# MOD-Y_V10.net
KiCad netlist of a schematic drawn in EAGLE
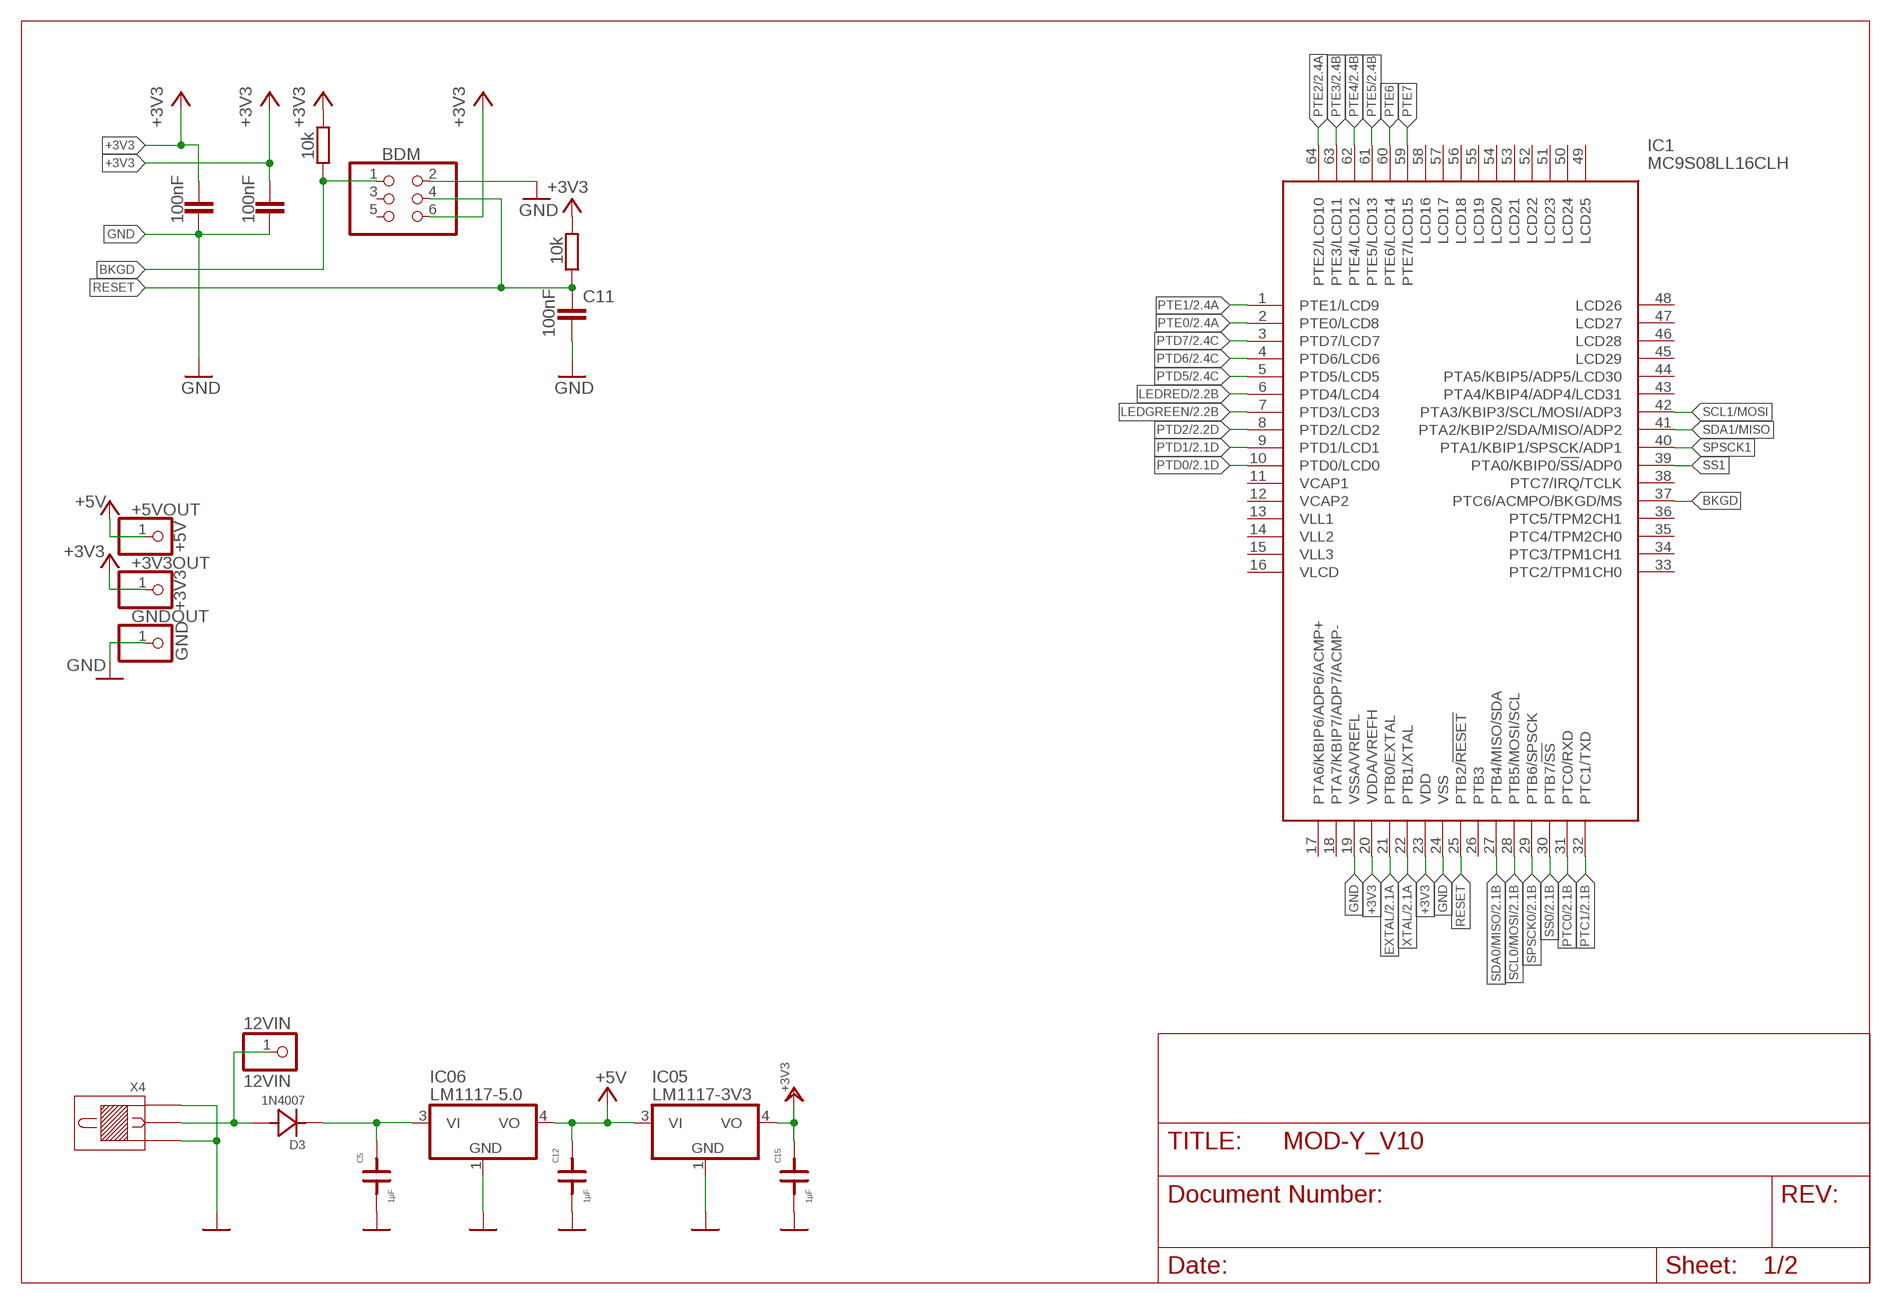
[diagram p0: schematic, sheet 1]
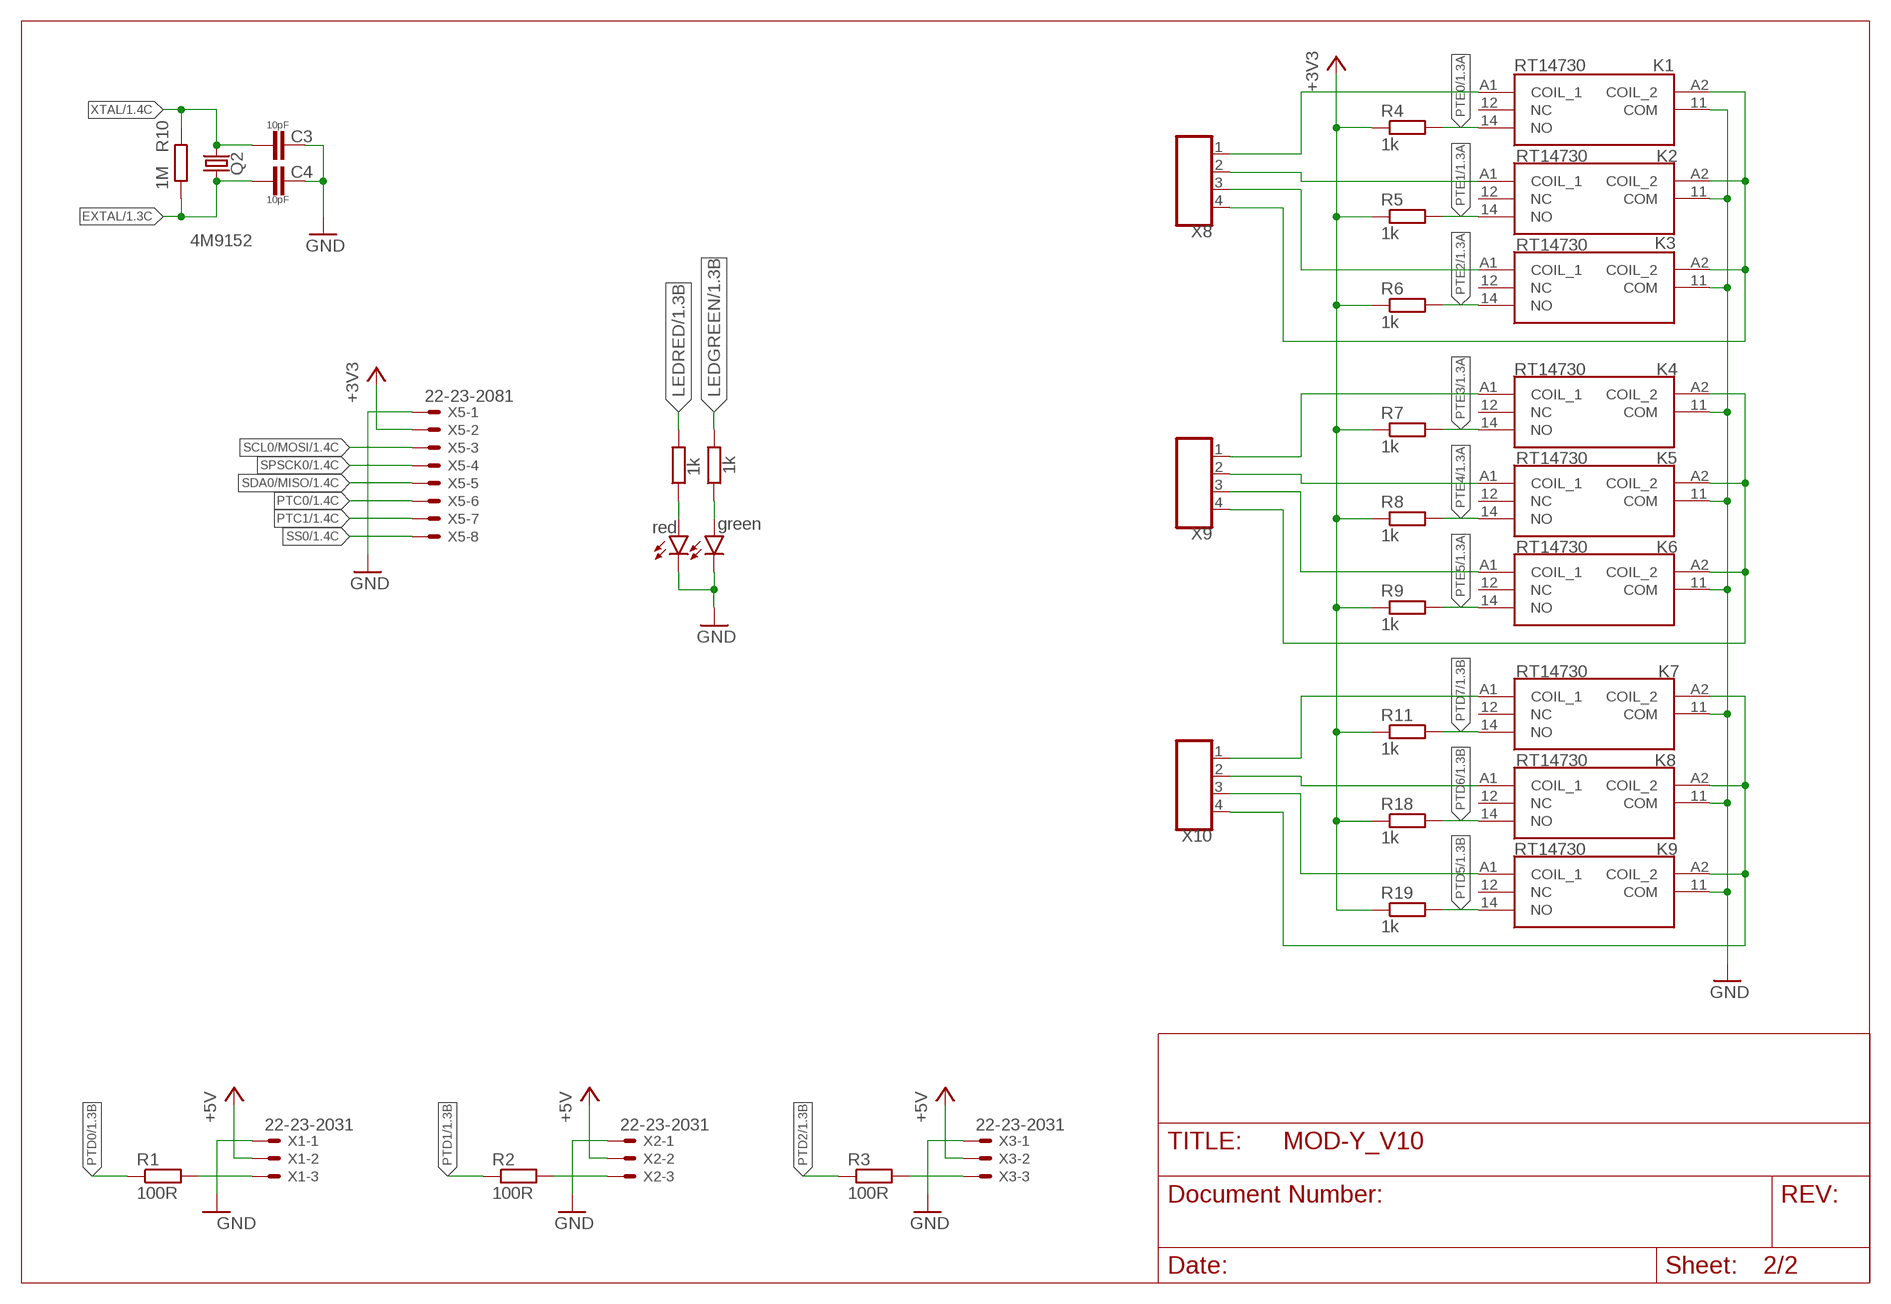
[diagram p1: schematic, sheet 2]

(export (version "E")
  (design (tool "Eeschema 10.0.6"))
  (components
    (comp (ref "+3V3OUT")
      (value "+3V3")
      (footprint "eagle-import:1X01")
      (libsource (lib "eagle-import") (part "PINHD-1X1"))
    )
    (comp (ref "+5VOUT")
      (value "+5V")
      (footprint "eagle-import:1X01")
      (libsource (lib "eagle-import") (part "PINHD-1X1"))
    )
    (comp (ref "12VIN")
      (value "12VIN")
      (footprint "eagle-import:1X01")
      (libsource (lib "eagle-import") (part "PINHD-1X1"))
    )
    (comp (ref "BDM")
      (value "PINHD-2X3")
      (footprint "eagle-import:2X03")
      (libsource (lib "eagle-import") (part "PINHD-2X3"))
    )
    (comp (ref "C5")
      (value "1µF")
      (footprint "eagle-import:0805F")
      (libsource (lib "eagle-import") (part "C1"))
    )
    (comp (ref "C9")
      (value "100nF")
      (footprint "eagle-import:C0805")
      (libsource (lib "eagle-import") (part "C-EUC0805"))
    )
    (comp (ref "C10")
      (value "100nF")
      (footprint "eagle-import:C0805")
      (libsource (lib "eagle-import") (part "C-EUC0805"))
    )
    (comp (ref "C11")
      (value "100nF")
      (footprint "eagle-import:C0805")
      (libsource (lib "eagle-import") (part "C-EUC0805"))
    )
    (comp (ref "C12")
      (value "1µF")
      (footprint "eagle-import:0805F")
      (libsource (lib "eagle-import") (part "C1"))
    )
    (comp (ref "C15")
      (value "1µF")
      (footprint "eagle-import:0805F")
      (libsource (lib "eagle-import") (part "C1"))
    )
    (comp (ref "D3")
      (value "1N4007")
      (footprint "eagle-import:MELF_B")
      (libsource (lib "eagle-import") (part "DHCMELF"))
    )
    (comp (ref "GNDOUT")
      (value "GND")
      (footprint "eagle-import:1X01")
      (libsource (lib "eagle-import") (part "PINHD-1X1"))
    )
    (comp (ref "IC1")
      (value "MC9S08LL16CLH")
      (footprint "eagle-import:QFP50P1200X1200X160-64N")
      (fields (field (name "MOUSER_PART_NUMBER") "841-MC9S08LL16CLH"))
      (libsource (lib "eagle-import") (part "MC9S08LL16CLH"))
    )
    (comp (ref "IC05")
      (value "LM1117-3V3")
      (footprint "eagle-import:DPAK")
      (libsource (lib "eagle-import") (part "LM1117DT"))
    )
    (comp (ref "IC06")
      (value "LM1117-5.0")
      (footprint "eagle-import:DPAK")
      (libsource (lib "eagle-import") (part "LM1117DT"))
    )
    (comp (ref "R16")
      (value "10k")
      (footprint "eagle-import:R0805")
      (libsource (lib "eagle-import") (part "R-EU_R0805"))
    )
    (comp (ref "R17")
      (value "10k")
      (footprint "eagle-import:R0805")
      (libsource (lib "eagle-import") (part "R-EU_R0805"))
    )
    (comp (ref "X4")
      (value "SPP")
      (footprint "eagle-import:SPP")
      (libsource (lib "eagle-import") (part "SPP"))
    )
    (comp (ref "C3")
      (value "10pF")
      (footprint "eagle-import:C0805")
      (libsource (lib "eagle-import") (part "C-EUC0805"))
    )
    (comp (ref "C4")
      (value "10pF")
      (footprint "eagle-import:C0805")
      (libsource (lib "eagle-import") (part "C-EUC0805"))
    )
    (comp (ref "K1")
      (value "RT14730")
      (footprint "eagle-import:RT14730")
      (fields (field (name "MANUFACTURER_PART_NUMBER") "rt14730"))
      (libsource (lib "eagle-import") (part "RT14730"))
    )
    (comp (ref "K2")
      (value "RT14730")
      (footprint "eagle-import:RT14730")
      (fields (field (name "MANUFACTURER_PART_NUMBER") "rt14730"))
      (libsource (lib "eagle-import") (part "RT14730"))
    )
    (comp (ref "K3")
      (value "RT14730")
      (footprint "eagle-import:RT14730")
      (fields (field (name "MANUFACTURER_PART_NUMBER") "rt14730"))
      (libsource (lib "eagle-import") (part "RT14730"))
    )
    (comp (ref "K4")
      (value "RT14730")
      (footprint "eagle-import:RT14730")
      (fields (field (name "MANUFACTURER_PART_NUMBER") "rt14730"))
      (libsource (lib "eagle-import") (part "RT14730"))
    )
    (comp (ref "K5")
      (value "RT14730")
      (footprint "eagle-import:RT14730")
      (fields (field (name "MANUFACTURER_PART_NUMBER") "rt14730"))
      (libsource (lib "eagle-import") (part "RT14730"))
    )
    (comp (ref "K6")
      (value "RT14730")
      (footprint "eagle-import:RT14730")
      (fields (field (name "MANUFACTURER_PART_NUMBER") "rt14730"))
      (libsource (lib "eagle-import") (part "RT14730"))
    )
    (comp (ref "K7")
      (value "RT14730")
      (footprint "eagle-import:RT14730")
      (fields (field (name "MANUFACTURER_PART_NUMBER") "rt14730"))
      (libsource (lib "eagle-import") (part "RT14730"))
    )
    (comp (ref "K8")
      (value "RT14730")
      (footprint "eagle-import:RT14730")
      (fields (field (name "MANUFACTURER_PART_NUMBER") "rt14730"))
      (libsource (lib "eagle-import") (part "RT14730"))
    )
    (comp (ref "K9")
      (value "RT14730")
      (footprint "eagle-import:RT14730")
      (fields (field (name "MANUFACTURER_PART_NUMBER") "rt14730"))
      (libsource (lib "eagle-import") (part "RT14730"))
    )
    (comp (ref "LED1")
      (value "green")
      (footprint "eagle-import:CHIP-LED0805")
      (libsource (lib "eagle-import") (part "LEDCHIP-LED0805"))
    )
    (comp (ref "LED2")
      (value "red")
      (footprint "eagle-import:CHIP-LED0805")
      (libsource (lib "eagle-import") (part "LEDCHIP-LED0805"))
    )
    (comp (ref "Q2")
      (value "4M9152")
      (footprint "eagle-import:HC49UP")
      (libsource (lib "eagle-import") (part "CRYSTALHC49UP"))
    )
    (comp (ref "R1")
      (value "100R")
      (footprint "eagle-import:R0805")
      (libsource (lib "eagle-import") (part "R-EU_R0805"))
    )
    (comp (ref "R2")
      (value "100R")
      (footprint "eagle-import:R0805")
      (libsource (lib "eagle-import") (part "R-EU_R0805"))
    )
    (comp (ref "R3")
      (value "100R")
      (footprint "eagle-import:R0805")
      (libsource (lib "eagle-import") (part "R-EU_R0805"))
    )
    (comp (ref "R4")
      (value "1k")
      (footprint "eagle-import:R0805")
      (libsource (lib "eagle-import") (part "R-EU_R0805"))
    )
    (comp (ref "R5")
      (value "1k")
      (footprint "eagle-import:R0805")
      (libsource (lib "eagle-import") (part "R-EU_R0805"))
    )
    (comp (ref "R6")
      (value "1k")
      (footprint "eagle-import:R0805")
      (libsource (lib "eagle-import") (part "R-EU_R0805"))
    )
    (comp (ref "R7")
      (value "1k")
      (footprint "eagle-import:R0805")
      (libsource (lib "eagle-import") (part "R-EU_R0805"))
    )
    (comp (ref "R8")
      (value "1k")
      (footprint "eagle-import:R0805")
      (libsource (lib "eagle-import") (part "R-EU_R0805"))
    )
    (comp (ref "R9")
      (value "1k")
      (footprint "eagle-import:R0805")
      (libsource (lib "eagle-import") (part "R-EU_R0805"))
    )
    (comp (ref "R10")
      (value "1M")
      (footprint "eagle-import:R0805")
      (libsource (lib "eagle-import") (part "R-EU_R0805"))
    )
    (comp (ref "R11")
      (value "1k")
      (footprint "eagle-import:R0805")
      (libsource (lib "eagle-import") (part "R-EU_R0805"))
    )
    (comp (ref "R12")
      (value "1k")
      (footprint "eagle-import:R0805")
      (libsource (lib "eagle-import") (part "R-EU_R0805"))
    )
    (comp (ref "R13")
      (value "1k")
      (footprint "eagle-import:R0805")
      (libsource (lib "eagle-import") (part "R-EU_R0805"))
    )
    (comp (ref "R18")
      (value "1k")
      (footprint "eagle-import:R0805")
      (libsource (lib "eagle-import") (part "R-EU_R0805"))
    )
    (comp (ref "R19")
      (value "1k")
      (footprint "eagle-import:R0805")
      (libsource (lib "eagle-import") (part "R-EU_R0805"))
    )
    (comp (ref "X1")
      (value "22-23-2031")
      (footprint "eagle-import:22-23-2031")
      (fields (field (name "MF") "MOLEX"))
      (libsource (lib "eagle-import") (part "22-23-2031"))
    )
    (comp (ref "X2")
      (value "22-23-2031")
      (footprint "eagle-import:22-23-2031")
      (fields (field (name "MF") "MOLEX"))
      (libsource (lib "eagle-import") (part "22-23-2031"))
    )
    (comp (ref "X3")
      (value "22-23-2031")
      (footprint "eagle-import:22-23-2031")
      (fields (field (name "MF") "MOLEX"))
      (libsource (lib "eagle-import") (part "22-23-2031"))
    )
    (comp (ref "X5")
      (value "22-23-2081")
      (footprint "eagle-import:22-23-2081")
      (fields (field (name "MF") "MOLEX"))
      (libsource (lib "eagle-import") (part "22-23-2081"))
    )
    (comp (ref "X8")
      (value "KLEMME4")
      (footprint "eagle-import:KLEMME4")
      (libsource (lib "eagle-import") (part "KLEMME4"))
    )
    (comp (ref "X9")
      (value "KLEMME4")
      (footprint "eagle-import:KLEMME4")
      (libsource (lib "eagle-import") (part "KLEMME4"))
    )
    (comp (ref "X10")
      (value "KLEMME4")
      (footprint "eagle-import:KLEMME4")
      (libsource (lib "eagle-import") (part "KLEMME4"))
    )
  )
  (nets
    (net (code "1") (name "+3V3") (class "Default")
      (node (ref "+3V3OUT") (pin "1") (pinfunction "1_1") (pintype "passive"))
      (node (ref "BDM") (pin "6") (pinfunction "6_6") (pintype "passive"))
      (node (ref "C10") (pin "1") (pinfunction "1_1") (pintype "passive"))
      (node (ref "C15") (pin "2") (pinfunction "2_2") (pintype "bidirectional"))
      (node (ref "C9") (pin "1") (pinfunction "1_1") (pintype "passive"))
      (node (ref "IC05") (pin "4") (pinfunction "VO_4") (pintype "output"))
      (node (ref "IC1") (pin "20") (pinfunction "VDDA/VREFH_20") (pintype "bidirectional"))
      (node (ref "IC1") (pin "23") (pinfunction "VDD_23") (pintype "bidirectional"))
      (node (ref "R11") (pin "1") (pinfunction "1_1") (pintype "passive"))
      (node (ref "R16") (pin "2") (pinfunction "2_2") (pintype "passive"))
      (node (ref "R17") (pin "2") (pinfunction "2_2") (pintype "passive"))
      (node (ref "R18") (pin "1") (pinfunction "1_1") (pintype "passive"))
      (node (ref "R19") (pin "1") (pinfunction "1_1") (pintype "passive"))
      (node (ref "R4") (pin "1") (pinfunction "1_1") (pintype "passive"))
      (node (ref "R5") (pin "1") (pinfunction "1_1") (pintype "passive"))
      (node (ref "R6") (pin "1") (pinfunction "1_1") (pintype "passive"))
      (node (ref "R7") (pin "1") (pinfunction "1_1") (pintype "passive"))
      (node (ref "R8") (pin "1") (pinfunction "1_1") (pintype "passive"))
      (node (ref "R9") (pin "1") (pinfunction "1_1") (pintype "passive"))
      (node (ref "X5") (pin "2") (pinfunction "S_2") (pintype "passive"))
    )
    (net (code "2") (name "+5V") (class "Default")
      (node (ref "+5VOUT") (pin "1") (pinfunction "1_1") (pintype "passive"))
      (node (ref "C12") (pin "2") (pinfunction "2_2") (pintype "bidirectional"))
      (node (ref "IC05") (pin "3") (pinfunction "VI_3") (pintype "input"))
      (node (ref "IC06") (pin "4") (pinfunction "VO_4") (pintype "output"))
      (node (ref "X1") (pin "2") (pinfunction "S_2") (pintype "passive"))
      (node (ref "X2") (pin "2") (pinfunction "S_2") (pintype "passive"))
      (node (ref "X3") (pin "2") (pinfunction "S_2") (pintype "passive"))
    )
    (net (code "3") (name "BKGD") (class "Default")
      (node (ref "BDM") (pin "1") (pinfunction "1_1") (pintype "passive"))
      (node (ref "IC1") (pin "37") (pinfunction "PTC6/ACMPO/BKGD/MS_37") (pintype "bidirectional"))
      (node (ref "R16") (pin "1") (pinfunction "1_1") (pintype "passive"))
    )
    (net (code "4") (name "EXTAL") (class "Default")
      (node (ref "C4") (pin "1") (pinfunction "1_1") (pintype "passive"))
      (node (ref "IC1") (pin "21") (pinfunction "PTB0/EXTAL_21") (pintype "bidirectional"))
      (node (ref "Q2") (pin "1") (pinfunction "1_1") (pintype "passive"))
      (node (ref "R10") (pin "1") (pinfunction "1_1") (pintype "passive"))
    )
    (net (code "5") (name "GND") (class "Default")
      (node (ref "BDM") (pin "2") (pinfunction "2_2") (pintype "passive"))
      (node (ref "C10") (pin "2") (pinfunction "2_2") (pintype "passive"))
      (node (ref "C11") (pin "2") (pinfunction "2_2") (pintype "passive"))
      (node (ref "C12") (pin "1") (pinfunction "1_1") (pintype "bidirectional"))
      (node (ref "C15") (pin "1") (pinfunction "1_1") (pintype "bidirectional"))
      (node (ref "C3") (pin "2") (pinfunction "2_2") (pintype "passive"))
      (node (ref "C4") (pin "2") (pinfunction "2_2") (pintype "passive"))
      (node (ref "C5") (pin "1") (pinfunction "1_1") (pintype "bidirectional"))
      (node (ref "C9") (pin "2") (pinfunction "2_2") (pintype "passive"))
      (node (ref "GNDOUT") (pin "1") (pinfunction "1_1") (pintype "passive"))
      (node (ref "IC05") (pin "1") (pinfunction "GND_1") (pintype "input"))
      (node (ref "IC06") (pin "1") (pinfunction "GND_1") (pintype "input"))
      (node (ref "IC1") (pin "19") (pinfunction "VSSA/VREFL_19") (pintype "bidirectional"))
      (node (ref "IC1") (pin "24") (pinfunction "VSS_24") (pintype "bidirectional"))
      (node (ref "K1") (pin "11") (pinfunction "COM_11") (pintype "bidirectional"))
      (node (ref "K2") (pin "11") (pinfunction "COM_11") (pintype "bidirectional"))
      (node (ref "K3") (pin "11") (pinfunction "COM_11") (pintype "bidirectional"))
      (node (ref "K4") (pin "11") (pinfunction "COM_11") (pintype "bidirectional"))
      (node (ref "K5") (pin "11") (pinfunction "COM_11") (pintype "bidirectional"))
      (node (ref "K6") (pin "11") (pinfunction "COM_11") (pintype "bidirectional"))
      (node (ref "K7") (pin "11") (pinfunction "COM_11") (pintype "bidirectional"))
      (node (ref "K8") (pin "11") (pinfunction "COM_11") (pintype "bidirectional"))
      (node (ref "K9") (pin "11") (pinfunction "COM_11") (pintype "bidirectional"))
      (node (ref "LED1") (pin "C") (pinfunction "C_C") (pintype "passive"))
      (node (ref "LED2") (pin "C") (pinfunction "C_C") (pintype "passive"))
      (node (ref "X1") (pin "1") (pinfunction "S_1") (pintype "passive"))
      (node (ref "X2") (pin "1") (pinfunction "S_1") (pintype "passive"))
      (node (ref "X3") (pin "1") (pinfunction "S_1") (pintype "passive"))
      (node (ref "X4") (pin "1") (pinfunction "1_1") (pintype "bidirectional"))
      (node (ref "X4") (pin "3") (pinfunction "3_3") (pintype "bidirectional"))
      (node (ref "X5") (pin "1") (pinfunction "S_1") (pintype "passive"))
    )
    (net (code "6") (name "LEDGREEN") (class "Default")
      (node (ref "IC1") (pin "7") (pinfunction "PTD3/LCD3_7") (pintype "bidirectional"))
      (node (ref "R13") (pin "2") (pinfunction "2_2") (pintype "passive"))
    )
    (net (code "7") (name "LEDRED") (class "Default")
      (node (ref "IC1") (pin "6") (pinfunction "PTD4/LCD4_6") (pintype "bidirectional"))
      (node (ref "R12") (pin "2") (pinfunction "2_2") (pintype "passive"))
    )
    (net (code "8") (name "Net-(12VIN-Pad1)") (class "Default")
      (node (ref "12VIN") (pin "1") (pinfunction "1_1") (pintype "passive"))
      (node (ref "D3") (pin "A") (pinfunction "A_A") (pintype "bidirectional"))
      (node (ref "X4") (pin "2") (pinfunction "2_2") (pintype "bidirectional"))
    )
    (net (code "9") (name "Net-(IC06-VI)") (class "Default")
      (node (ref "C5") (pin "2") (pinfunction "2_2") (pintype "bidirectional"))
      (node (ref "D3") (pin "K") (pinfunction "K_K") (pintype "bidirectional"))
      (node (ref "IC06") (pin "3") (pinfunction "VI_3") (pintype "input"))
    )
    (net (code "10") (name "Net-(K1-COIL_1)") (class "Default")
      (node (ref "K1") (pin "A1") (pinfunction "COIL_1_A1") (pintype "bidirectional"))
      (node (ref "X8") (pin "1") (pinfunction "1_1") (pintype "bidirectional"))
    )
    (net (code "11") (name "Net-(K1-COIL_2)") (class "Default")
      (node (ref "K1") (pin "A2") (pinfunction "COIL_2_A2") (pintype "bidirectional"))
      (node (ref "K2") (pin "A2") (pinfunction "COIL_2_A2") (pintype "bidirectional"))
      (node (ref "K3") (pin "A2") (pinfunction "COIL_2_A2") (pintype "bidirectional"))
      (node (ref "X8") (pin "4") (pinfunction "4_4") (pintype "bidirectional"))
    )
    (net (code "12") (name "Net-(K2-COIL_1)") (class "Default")
      (node (ref "K2") (pin "A1") (pinfunction "COIL_1_A1") (pintype "bidirectional"))
      (node (ref "X8") (pin "2") (pinfunction "2_2") (pintype "bidirectional"))
    )
    (net (code "13") (name "Net-(K3-COIL_1)") (class "Default")
      (node (ref "K3") (pin "A1") (pinfunction "COIL_1_A1") (pintype "bidirectional"))
      (node (ref "X8") (pin "3") (pinfunction "3_3") (pintype "bidirectional"))
    )
    (net (code "14") (name "Net-(K4-COIL_1)") (class "Default")
      (node (ref "K4") (pin "A1") (pinfunction "COIL_1_A1") (pintype "bidirectional"))
      (node (ref "X9") (pin "1") (pinfunction "1_1") (pintype "bidirectional"))
    )
    (net (code "15") (name "Net-(K4-COIL_2)") (class "Default")
      (node (ref "K4") (pin "A2") (pinfunction "COIL_2_A2") (pintype "bidirectional"))
      (node (ref "K5") (pin "A2") (pinfunction "COIL_2_A2") (pintype "bidirectional"))
      (node (ref "K6") (pin "A2") (pinfunction "COIL_2_A2") (pintype "bidirectional"))
      (node (ref "X9") (pin "4") (pinfunction "4_4") (pintype "bidirectional"))
    )
    (net (code "16") (name "Net-(K5-COIL_1)") (class "Default")
      (node (ref "K5") (pin "A1") (pinfunction "COIL_1_A1") (pintype "bidirectional"))
      (node (ref "X9") (pin "2") (pinfunction "2_2") (pintype "bidirectional"))
    )
    (net (code "17") (name "Net-(K6-COIL_1)") (class "Default")
      (node (ref "K6") (pin "A1") (pinfunction "COIL_1_A1") (pintype "bidirectional"))
      (node (ref "X9") (pin "3") (pinfunction "3_3") (pintype "bidirectional"))
    )
    (net (code "18") (name "Net-(K7-COIL_1)") (class "Default")
      (node (ref "K7") (pin "A1") (pinfunction "COIL_1_A1") (pintype "bidirectional"))
      (node (ref "X10") (pin "1") (pinfunction "1_1") (pintype "bidirectional"))
    )
    (net (code "19") (name "Net-(K7-COIL_2)") (class "Default")
      (node (ref "K7") (pin "A2") (pinfunction "COIL_2_A2") (pintype "bidirectional"))
      (node (ref "K8") (pin "A2") (pinfunction "COIL_2_A2") (pintype "bidirectional"))
      (node (ref "K9") (pin "A2") (pinfunction "COIL_2_A2") (pintype "bidirectional"))
      (node (ref "X10") (pin "4") (pinfunction "4_4") (pintype "bidirectional"))
    )
    (net (code "20") (name "Net-(K8-COIL_1)") (class "Default")
      (node (ref "K8") (pin "A1") (pinfunction "COIL_1_A1") (pintype "bidirectional"))
      (node (ref "X10") (pin "2") (pinfunction "2_2") (pintype "bidirectional"))
    )
    (net (code "21") (name "Net-(K9-COIL_1)") (class "Default")
      (node (ref "K9") (pin "A1") (pinfunction "COIL_1_A1") (pintype "bidirectional"))
      (node (ref "X10") (pin "3") (pinfunction "3_3") (pintype "bidirectional"))
    )
    (net (code "22") (name "Net-(LED1-PadA)") (class "Default")
      (node (ref "LED1") (pin "A") (pinfunction "A_A") (pintype "passive"))
      (node (ref "R13") (pin "1") (pinfunction "1_1") (pintype "passive"))
    )
    (net (code "23") (name "Net-(LED2-PadA)") (class "Default")
      (node (ref "LED2") (pin "A") (pinfunction "A_A") (pintype "passive"))
      (node (ref "R12") (pin "1") (pinfunction "1_1") (pintype "passive"))
    )
    (net (code "24") (name "Net-(X1C-S)") (class "Default")
      (node (ref "R1") (pin "2") (pinfunction "2_2") (pintype "passive"))
      (node (ref "X1") (pin "3") (pinfunction "S_3") (pintype "passive"))
    )
    (net (code "25") (name "Net-(X2C-S)") (class "Default")
      (node (ref "R2") (pin "2") (pinfunction "2_2") (pintype "passive"))
      (node (ref "X2") (pin "3") (pinfunction "S_3") (pintype "passive"))
    )
    (net (code "26") (name "Net-(X3C-S)") (class "Default")
      (node (ref "R3") (pin "2") (pinfunction "2_2") (pintype "passive"))
      (node (ref "X3") (pin "3") (pinfunction "S_3") (pintype "passive"))
    )
    (net (code "27") (name "PTC0") (class "Default")
      (node (ref "IC1") (pin "31") (pinfunction "PTC0/RXD_31") (pintype "bidirectional"))
      (node (ref "X5") (pin "6") (pinfunction "S_6") (pintype "passive"))
    )
    (net (code "28") (name "PTC1") (class "Default")
      (node (ref "IC1") (pin "32") (pinfunction "PTC1/TXD_32") (pintype "bidirectional"))
      (node (ref "X5") (pin "7") (pinfunction "S_7") (pintype "passive"))
    )
    (net (code "29") (name "PTD0") (class "Default")
      (node (ref "IC1") (pin "10") (pinfunction "PTD0/LCD0_10") (pintype "bidirectional"))
      (node (ref "R1") (pin "1") (pinfunction "1_1") (pintype "passive"))
    )
    (net (code "30") (name "PTD1") (class "Default")
      (node (ref "IC1") (pin "9") (pinfunction "PTD1/LCD1_9") (pintype "bidirectional"))
      (node (ref "R2") (pin "1") (pinfunction "1_1") (pintype "passive"))
    )
    (net (code "31") (name "PTD2") (class "Default")
      (node (ref "IC1") (pin "8") (pinfunction "PTD2/LCD2_8") (pintype "bidirectional"))
      (node (ref "R3") (pin "1") (pinfunction "1_1") (pintype "passive"))
    )
    (net (code "32") (name "PTD5") (class "Default")
      (node (ref "IC1") (pin "5") (pinfunction "PTD5/LCD5_5") (pintype "bidirectional"))
      (node (ref "K9") (pin "14") (pinfunction "NO_14") (pintype "bidirectional"))
      (node (ref "R19") (pin "2") (pinfunction "2_2") (pintype "passive"))
    )
    (net (code "33") (name "PTD6") (class "Default")
      (node (ref "IC1") (pin "4") (pinfunction "PTD6/LCD6_4") (pintype "bidirectional"))
      (node (ref "K8") (pin "14") (pinfunction "NO_14") (pintype "bidirectional"))
      (node (ref "R18") (pin "2") (pinfunction "2_2") (pintype "passive"))
    )
    (net (code "34") (name "PTD7") (class "Default")
      (node (ref "IC1") (pin "3") (pinfunction "PTD7/LCD7_3") (pintype "bidirectional"))
      (node (ref "K7") (pin "14") (pinfunction "NO_14") (pintype "bidirectional"))
      (node (ref "R11") (pin "2") (pinfunction "2_2") (pintype "passive"))
    )
    (net (code "35") (name "PTE0") (class "Default")
      (node (ref "IC1") (pin "2") (pinfunction "PTE0/LCD8_2") (pintype "bidirectional"))
      (node (ref "K1") (pin "14") (pinfunction "NO_14") (pintype "bidirectional"))
      (node (ref "R4") (pin "2") (pinfunction "2_2") (pintype "passive"))
    )
    (net (code "36") (name "PTE1") (class "Default")
      (node (ref "IC1") (pin "1") (pinfunction "PTE1/LCD9_1") (pintype "bidirectional"))
      (node (ref "K2") (pin "14") (pinfunction "NO_14") (pintype "bidirectional"))
      (node (ref "R5") (pin "2") (pinfunction "2_2") (pintype "passive"))
    )
    (net (code "37") (name "PTE2") (class "Default")
      (node (ref "IC1") (pin "64") (pinfunction "PTE2/LCD10_64") (pintype "bidirectional"))
      (node (ref "K3") (pin "14") (pinfunction "NO_14") (pintype "bidirectional"))
      (node (ref "R6") (pin "2") (pinfunction "2_2") (pintype "passive"))
    )
    (net (code "38") (name "PTE3") (class "Default")
      (node (ref "IC1") (pin "63") (pinfunction "PTE3/LCD11_63") (pintype "bidirectional"))
      (node (ref "K4") (pin "14") (pinfunction "NO_14") (pintype "bidirectional"))
      (node (ref "R7") (pin "2") (pinfunction "2_2") (pintype "passive"))
    )
    (net (code "39") (name "PTE4") (class "Default")
      (node (ref "IC1") (pin "62") (pinfunction "PTE4/LCD12_62") (pintype "bidirectional"))
      (node (ref "K5") (pin "14") (pinfunction "NO_14") (pintype "bidirectional"))
      (node (ref "R8") (pin "2") (pinfunction "2_2") (pintype "passive"))
    )
    (net (code "40") (name "PTE5") (class "Default")
      (node (ref "IC1") (pin "61") (pinfunction "PTE5/LCD13_61") (pintype "bidirectional"))
      (node (ref "K6") (pin "14") (pinfunction "NO_14") (pintype "bidirectional"))
      (node (ref "R9") (pin "2") (pinfunction "2_2") (pintype "passive"))
    )
    (net (code "41") (name "PTE6") (class "Default")
      (node (ref "IC1") (pin "60") (pinfunction "PTE6/LCD14_60") (pintype "bidirectional"))
    )
    (net (code "42") (name "PTE7") (class "Default")
      (node (ref "IC1") (pin "59") (pinfunction "PTE7/LCD15_59") (pintype "bidirectional"))
    )
    (net (code "43") (name "RESET") (class "Default")
      (node (ref "BDM") (pin "4") (pinfunction "4_4") (pintype "passive"))
      (node (ref "C11") (pin "1") (pinfunction "1_1") (pintype "passive"))
      (node (ref "IC1") (pin "25") (pinfunction "PTB2/~{RESET}_25") (pintype "bidirectional"))
      (node (ref "R17") (pin "1") (pinfunction "1_1") (pintype "passive"))
    )
    (net (code "44") (name "SCL0{slash}MOSI") (class "Default")
      (node (ref "IC1") (pin "28") (pinfunction "PTB5/MOSI/SCL_28") (pintype "bidirectional"))
      (node (ref "X5") (pin "3") (pinfunction "S_3") (pintype "passive"))
    )
    (net (code "45") (name "SCL1{slash}MOSI") (class "Default")
      (node (ref "IC1") (pin "42") (pinfunction "PTA3/KBIP3/SCL/MOSI/ADP3_42") (pintype "bidirectional"))
    )
    (net (code "46") (name "SDA0{slash}MISO") (class "Default")
      (node (ref "IC1") (pin "27") (pinfunction "PTB4/MISO/SDA_27") (pintype "bidirectional"))
      (node (ref "X5") (pin "5") (pinfunction "S_5") (pintype "passive"))
    )
    (net (code "47") (name "SDA1{slash}MISO") (class "Default")
      (node (ref "IC1") (pin "41") (pinfunction "PTA2/KBIP2/SDA/MISO/ADP2_41") (pintype "bidirectional"))
    )
    (net (code "48") (name "SPSCK0") (class "Default")
      (node (ref "IC1") (pin "29") (pinfunction "PTB6/SPSCK_29") (pintype "bidirectional"))
      (node (ref "X5") (pin "4") (pinfunction "S_4") (pintype "passive"))
    )
    (net (code "49") (name "SPSCK1") (class "Default")
      (node (ref "IC1") (pin "40") (pinfunction "PTA1/KBIP1/SPSCK/ADP1_40") (pintype "bidirectional"))
    )
    (net (code "50") (name "SS0") (class "Default")
      (node (ref "IC1") (pin "30") (pinfunction "PTB7/~{SS}_30") (pintype "bidirectional"))
      (node (ref "X5") (pin "8") (pinfunction "S_8") (pintype "passive"))
    )
    (net (code "51") (name "SS1") (class "Default")
      (node (ref "IC1") (pin "39") (pinfunction "PTA0/KBIP0/~{SS}/ADP0_39") (pintype "bidirectional"))
    )
    (net (code "52") (name "XTAL") (class "Default")
      (node (ref "C3") (pin "1") (pinfunction "1_1") (pintype "passive"))
      (node (ref "IC1") (pin "22") (pinfunction "PTB1/XTAL_22") (pintype "bidirectional"))
      (node (ref "Q2") (pin "2") (pinfunction "2_2") (pintype "passive"))
      (node (ref "R10") (pin "2") (pinfunction "2_2") (pintype "passive"))
    )
    (net (code "53") (name "unconnected-(BDM-Pad3)") (class "Default")
      (node (ref "BDM") (pin "3") (pinfunction "3_3") (pintype "passive"))
    )
    (net (code "54") (name "unconnected-(BDM-Pad5)") (class "Default")
      (node (ref "BDM") (pin "5") (pinfunction "5_5") (pintype "passive"))
    )
    (net (code "55") (name "unconnected-(IC1-LCD16-Pad58)") (class "Default")
      (node (ref "IC1") (pin "58") (pinfunction "LCD16_58") (pintype "bidirectional"))
    )
    (net (code "56") (name "unconnected-(IC1-LCD17-Pad57)") (class "Default")
      (node (ref "IC1") (pin "57") (pinfunction "LCD17_57") (pintype "bidirectional"))
    )
    (net (code "57") (name "unconnected-(IC1-LCD18-Pad56)") (class "Default")
      (node (ref "IC1") (pin "56") (pinfunction "LCD18_56") (pintype "bidirectional"))
    )
    (net (code "58") (name "unconnected-(IC1-LCD19-Pad55)") (class "Default")
      (node (ref "IC1") (pin "55") (pinfunction "LCD19_55") (pintype "bidirectional"))
    )
    (net (code "59") (name "unconnected-(IC1-LCD20-Pad54)") (class "Default")
      (node (ref "IC1") (pin "54") (pinfunction "LCD20_54") (pintype "bidirectional"))
    )
    (net (code "60") (name "unconnected-(IC1-LCD21-Pad53)") (class "Default")
      (node (ref "IC1") (pin "53") (pinfunction "LCD21_53") (pintype "bidirectional"))
    )
    (net (code "61") (name "unconnected-(IC1-LCD22-Pad52)") (class "Default")
      (node (ref "IC1") (pin "52") (pinfunction "LCD22_52") (pintype "bidirectional"))
    )
    (net (code "62") (name "unconnected-(IC1-LCD23-Pad51)") (class "Default")
      (node (ref "IC1") (pin "51") (pinfunction "LCD23_51") (pintype "bidirectional"))
    )
    (net (code "63") (name "unconnected-(IC1-LCD24-Pad50)") (class "Default")
      (node (ref "IC1") (pin "50") (pinfunction "LCD24_50") (pintype "bidirectional"))
    )
    (net (code "64") (name "unconnected-(IC1-LCD25-Pad49)") (class "Default")
      (node (ref "IC1") (pin "49") (pinfunction "LCD25_49") (pintype "bidirectional"))
    )
    (net (code "65") (name "unconnected-(IC1-LCD26-Pad48)") (class "Default")
      (node (ref "IC1") (pin "48") (pinfunction "LCD26_48") (pintype "bidirectional"))
    )
    (net (code "66") (name "unconnected-(IC1-LCD27-Pad47)") (class "Default")
      (node (ref "IC1") (pin "47") (pinfunction "LCD27_47") (pintype "bidirectional"))
    )
    (net (code "67") (name "unconnected-(IC1-LCD28-Pad46)") (class "Default")
      (node (ref "IC1") (pin "46") (pinfunction "LCD28_46") (pintype "bidirectional"))
    )
    (net (code "68") (name "unconnected-(IC1-LCD29-Pad45)") (class "Default")
      (node (ref "IC1") (pin "45") (pinfunction "LCD29_45") (pintype "bidirectional"))
    )
    (net (code "69") (name "unconnected-(IC1-PTA4{slash}KBIP4{slash}ADP4{slash}LCD31-Pad43)") (class "Default")
      (node (ref "IC1") (pin "43") (pinfunction "PTA4/KBIP4/ADP4/LCD31_43") (pintype "bidirectional"))
    )
    (net (code "70") (name "unconnected-(IC1-PTA5{slash}KBIP5{slash}ADP5{slash}LCD30-Pad44)") (class "Default")
      (node (ref "IC1") (pin "44") (pinfunction "PTA5/KBIP5/ADP5/LCD30_44") (pintype "bidirectional"))
    )
    (net (code "71") (name "unconnected-(IC1-PTA6{slash}KBIP6{slash}ADP6{slash}ACMP+-Pad17)") (class "Default")
      (node (ref "IC1") (pin "17") (pinfunction "PTA6/KBIP6/ADP6/ACMP+_17") (pintype "bidirectional"))
    )
    (net (code "72") (name "unconnected-(IC1-PTA7{slash}KBIP7{slash}ADP7{slash}ACMP--Pad18)") (class "Default")
      (node (ref "IC1") (pin "18") (pinfunction "PTA7/KBIP7/ADP7/ACMP-_18") (pintype "bidirectional"))
    )
    (net (code "73") (name "unconnected-(IC1-PTB3-Pad26)") (class "Default")
      (node (ref "IC1") (pin "26") (pinfunction "PTB3_26") (pintype "bidirectional"))
    )
    (net (code "74") (name "unconnected-(IC1-PTC2{slash}TPM1CH0-Pad33)") (class "Default")
      (node (ref "IC1") (pin "33") (pinfunction "PTC2/TPM1CH0_33") (pintype "bidirectional"))
    )
    (net (code "75") (name "unconnected-(IC1-PTC3{slash}TPM1CH1-Pad34)") (class "Default")
      (node (ref "IC1") (pin "34") (pinfunction "PTC3/TPM1CH1_34") (pintype "bidirectional"))
    )
    (net (code "76") (name "unconnected-(IC1-PTC4{slash}TPM2CH0-Pad35)") (class "Default")
      (node (ref "IC1") (pin "35") (pinfunction "PTC4/TPM2CH0_35") (pintype "bidirectional"))
    )
    (net (code "77") (name "unconnected-(IC1-PTC5{slash}TPM2CH1-Pad36)") (class "Default")
      (node (ref "IC1") (pin "36") (pinfunction "PTC5/TPM2CH1_36") (pintype "bidirectional"))
    )
    (net (code "78") (name "unconnected-(IC1-PTC7{slash}IRQ{slash}TCLK-Pad38)") (class "Default")
      (node (ref "IC1") (pin "38") (pinfunction "PTC7/IRQ/TCLK_38") (pintype "bidirectional"))
    )
    (net (code "79") (name "unconnected-(IC1-VCAP1-Pad11)") (class "Default")
      (node (ref "IC1") (pin "11") (pinfunction "VCAP1_11") (pintype "bidirectional"))
    )
    (net (code "80") (name "unconnected-(IC1-VCAP2-Pad12)") (class "Default")
      (node (ref "IC1") (pin "12") (pinfunction "VCAP2_12") (pintype "bidirectional"))
    )
    (net (code "81") (name "unconnected-(IC1-VLCD-Pad16)") (class "Default")
      (node (ref "IC1") (pin "16") (pinfunction "VLCD_16") (pintype "bidirectional"))
    )
    (net (code "82") (name "unconnected-(IC1-VLL1-Pad13)") (class "Default")
      (node (ref "IC1") (pin "13") (pinfunction "VLL1_13") (pintype "bidirectional"))
    )
    (net (code "83") (name "unconnected-(IC1-VLL2-Pad14)") (class "Default")
      (node (ref "IC1") (pin "14") (pinfunction "VLL2_14") (pintype "bidirectional"))
    )
    (net (code "84") (name "unconnected-(IC1-VLL3-Pad15)") (class "Default")
      (node (ref "IC1") (pin "15") (pinfunction "VLL3_15") (pintype "bidirectional"))
    )
    (net (code "85") (name "unconnected-(K1-NC-Pad12)") (class "Default")
      (node (ref "K1") (pin "12") (pinfunction "NC_12") (pintype "no_connect"))
    )
    (net (code "86") (name "unconnected-(K2-NC-Pad12)") (class "Default")
      (node (ref "K2") (pin "12") (pinfunction "NC_12") (pintype "no_connect"))
    )
    (net (code "87") (name "unconnected-(K3-NC-Pad12)") (class "Default")
      (node (ref "K3") (pin "12") (pinfunction "NC_12") (pintype "no_connect"))
    )
    (net (code "88") (name "unconnected-(K4-NC-Pad12)") (class "Default")
      (node (ref "K4") (pin "12") (pinfunction "NC_12") (pintype "no_connect"))
    )
    (net (code "89") (name "unconnected-(K5-NC-Pad12)") (class "Default")
      (node (ref "K5") (pin "12") (pinfunction "NC_12") (pintype "no_connect"))
    )
    (net (code "90") (name "unconnected-(K6-NC-Pad12)") (class "Default")
      (node (ref "K6") (pin "12") (pinfunction "NC_12") (pintype "no_connect"))
    )
    (net (code "91") (name "unconnected-(K7-NC-Pad12)") (class "Default")
      (node (ref "K7") (pin "12") (pinfunction "NC_12") (pintype "no_connect"))
    )
    (net (code "92") (name "unconnected-(K8-NC-Pad12)") (class "Default")
      (node (ref "K8") (pin "12") (pinfunction "NC_12") (pintype "no_connect"))
    )
    (net (code "93") (name "unconnected-(K9-NC-Pad12)") (class "Default")
      (node (ref "K9") (pin "12") (pinfunction "NC_12") (pintype "no_connect"))
    )
  )
)
